# 04_-_RGB_LED_MATRIX.net
KiCad netlist of a schematic drawn in Altium Designer
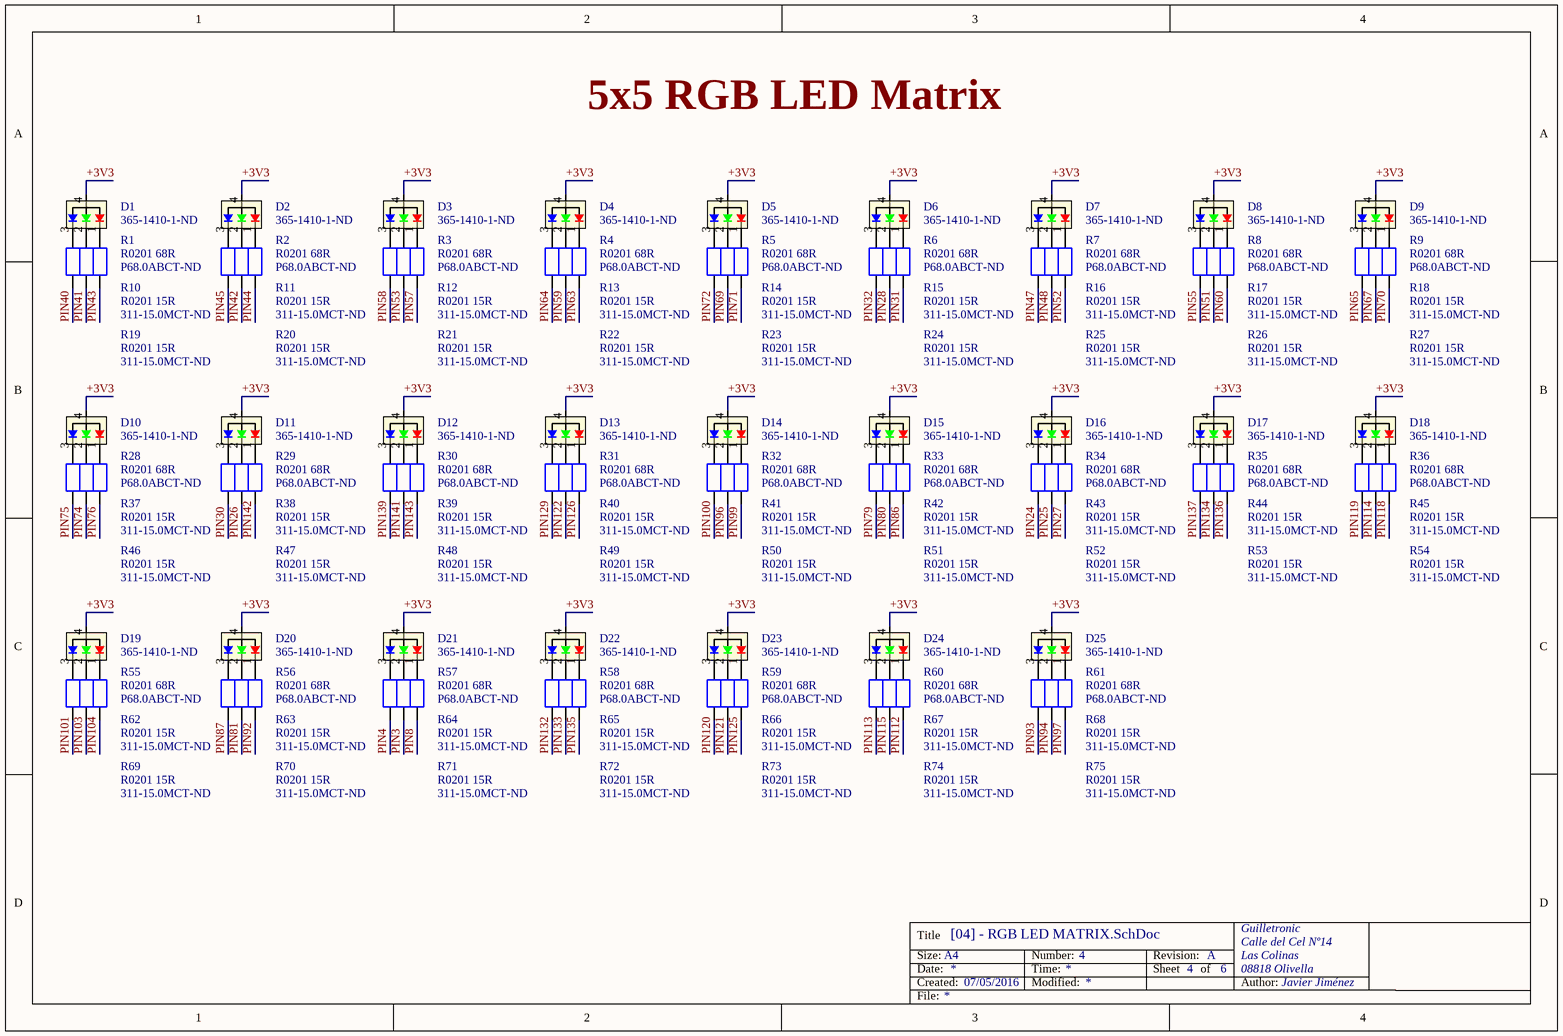
[diagram p0: [04] - RGB LED MATRIX.SchDoc]

(export (version "E")
  (design (tool "Eeschema 10.0.6"))
  (components
    (comp (ref "D1")
      (value "LED RGB")
      (footprint "LED RGB")
      (description "LED RGB DIFFUSED 4SMD R/A")
      (fields (field (name "SUPPLIER PART NUMBER 1") "365-1410-1-ND"))
      (libsource (lib "GUILLETRONIC") (part "LED RGB"))
    )
    (comp (ref "D2")
      (value "LED RGB")
      (footprint "LED RGB")
      (description "LED RGB DIFFUSED 4SMD R/A")
      (fields (field (name "SUPPLIER PART NUMBER 1") "365-1410-1-ND"))
      (libsource (lib "GUILLETRONIC") (part "LED RGB"))
    )
    (comp (ref "D3")
      (value "LED RGB")
      (footprint "LED RGB")
      (description "LED RGB DIFFUSED 4SMD R/A")
      (fields (field (name "SUPPLIER PART NUMBER 1") "365-1410-1-ND"))
      (libsource (lib "GUILLETRONIC") (part "LED RGB"))
    )
    (comp (ref "D4")
      (value "LED RGB")
      (footprint "LED RGB")
      (description "LED RGB DIFFUSED 4SMD R/A")
      (fields (field (name "SUPPLIER PART NUMBER 1") "365-1410-1-ND"))
      (libsource (lib "GUILLETRONIC") (part "LED RGB"))
    )
    (comp (ref "D5")
      (value "LED RGB")
      (footprint "LED RGB")
      (description "LED RGB DIFFUSED 4SMD R/A")
      (fields (field (name "SUPPLIER PART NUMBER 1") "365-1410-1-ND"))
      (libsource (lib "GUILLETRONIC") (part "LED RGB"))
    )
    (comp (ref "D6")
      (value "LED RGB")
      (footprint "LED RGB")
      (description "LED RGB DIFFUSED 4SMD R/A")
      (fields (field (name "SUPPLIER PART NUMBER 1") "365-1410-1-ND"))
      (libsource (lib "GUILLETRONIC") (part "LED RGB"))
    )
    (comp (ref "D7")
      (value "LED RGB")
      (footprint "LED RGB")
      (description "LED RGB DIFFUSED 4SMD R/A")
      (fields (field (name "SUPPLIER PART NUMBER 1") "365-1410-1-ND"))
      (libsource (lib "GUILLETRONIC") (part "LED RGB"))
    )
    (comp (ref "D8")
      (value "LED RGB")
      (footprint "LED RGB")
      (description "LED RGB DIFFUSED 4SMD R/A")
      (fields (field (name "SUPPLIER PART NUMBER 1") "365-1410-1-ND"))
      (libsource (lib "GUILLETRONIC") (part "LED RGB"))
    )
    (comp (ref "D9")
      (value "LED RGB")
      (footprint "LED RGB")
      (description "LED RGB DIFFUSED 4SMD R/A")
      (fields (field (name "SUPPLIER PART NUMBER 1") "365-1410-1-ND"))
      (libsource (lib "GUILLETRONIC") (part "LED RGB"))
    )
    (comp (ref "D10")
      (value "LED RGB")
      (footprint "LED RGB")
      (description "LED RGB DIFFUSED 4SMD R/A")
      (fields (field (name "SUPPLIER PART NUMBER 1") "365-1410-1-ND"))
      (libsource (lib "GUILLETRONIC") (part "LED RGB"))
    )
    (comp (ref "D11")
      (value "LED RGB")
      (footprint "LED RGB")
      (description "LED RGB DIFFUSED 4SMD R/A")
      (fields (field (name "SUPPLIER PART NUMBER 1") "365-1410-1-ND"))
      (libsource (lib "GUILLETRONIC") (part "LED RGB"))
    )
    (comp (ref "D12")
      (value "LED RGB")
      (footprint "LED RGB")
      (description "LED RGB DIFFUSED 4SMD R/A")
      (fields (field (name "SUPPLIER PART NUMBER 1") "365-1410-1-ND"))
      (libsource (lib "GUILLETRONIC") (part "LED RGB"))
    )
    (comp (ref "D13")
      (value "LED RGB")
      (footprint "LED RGB")
      (description "LED RGB DIFFUSED 4SMD R/A")
      (fields (field (name "SUPPLIER PART NUMBER 1") "365-1410-1-ND"))
      (libsource (lib "GUILLETRONIC") (part "LED RGB"))
    )
    (comp (ref "D14")
      (value "LED RGB")
      (footprint "LED RGB")
      (description "LED RGB DIFFUSED 4SMD R/A")
      (fields (field (name "SUPPLIER PART NUMBER 1") "365-1410-1-ND"))
      (libsource (lib "GUILLETRONIC") (part "LED RGB"))
    )
    (comp (ref "D15")
      (value "LED RGB")
      (footprint "LED RGB")
      (description "LED RGB DIFFUSED 4SMD R/A")
      (fields (field (name "SUPPLIER PART NUMBER 1") "365-1410-1-ND"))
      (libsource (lib "GUILLETRONIC") (part "LED RGB"))
    )
    (comp (ref "D16")
      (value "LED RGB")
      (footprint "LED RGB")
      (description "LED RGB DIFFUSED 4SMD R/A")
      (fields (field (name "SUPPLIER PART NUMBER 1") "365-1410-1-ND"))
      (libsource (lib "GUILLETRONIC") (part "LED RGB"))
    )
    (comp (ref "D17")
      (value "LED RGB")
      (footprint "LED RGB")
      (description "LED RGB DIFFUSED 4SMD R/A")
      (fields (field (name "SUPPLIER PART NUMBER 1") "365-1410-1-ND"))
      (libsource (lib "GUILLETRONIC") (part "LED RGB"))
    )
    (comp (ref "D18")
      (value "LED RGB")
      (footprint "LED RGB")
      (description "LED RGB DIFFUSED 4SMD R/A")
      (fields (field (name "SUPPLIER PART NUMBER 1") "365-1410-1-ND"))
      (libsource (lib "GUILLETRONIC") (part "LED RGB"))
    )
    (comp (ref "D19")
      (value "LED RGB")
      (footprint "LED RGB")
      (description "LED RGB DIFFUSED 4SMD R/A")
      (fields (field (name "SUPPLIER PART NUMBER 1") "365-1410-1-ND"))
      (libsource (lib "GUILLETRONIC") (part "LED RGB"))
    )
    (comp (ref "D20")
      (value "LED RGB")
      (footprint "LED RGB")
      (description "LED RGB DIFFUSED 4SMD R/A")
      (fields (field (name "SUPPLIER PART NUMBER 1") "365-1410-1-ND"))
      (libsource (lib "GUILLETRONIC") (part "LED RGB"))
    )
    (comp (ref "D21")
      (value "LED RGB")
      (footprint "LED RGB")
      (description "LED RGB DIFFUSED 4SMD R/A")
      (fields (field (name "SUPPLIER PART NUMBER 1") "365-1410-1-ND"))
      (libsource (lib "GUILLETRONIC") (part "LED RGB"))
    )
    (comp (ref "D22")
      (value "LED RGB")
      (footprint "LED RGB")
      (description "LED RGB DIFFUSED 4SMD R/A")
      (fields (field (name "SUPPLIER PART NUMBER 1") "365-1410-1-ND"))
      (libsource (lib "GUILLETRONIC") (part "LED RGB"))
    )
    (comp (ref "D23")
      (value "LED RGB")
      (footprint "LED RGB")
      (description "LED RGB DIFFUSED 4SMD R/A")
      (fields (field (name "SUPPLIER PART NUMBER 1") "365-1410-1-ND"))
      (libsource (lib "GUILLETRONIC") (part "LED RGB"))
    )
    (comp (ref "D24")
      (value "LED RGB")
      (footprint "LED RGB")
      (description "LED RGB DIFFUSED 4SMD R/A")
      (fields (field (name "SUPPLIER PART NUMBER 1") "365-1410-1-ND"))
      (libsource (lib "GUILLETRONIC") (part "LED RGB"))
    )
    (comp (ref "D25")
      (value "LED RGB")
      (footprint "LED RGB")
      (description "LED RGB DIFFUSED 4SMD R/A")
      (fields (field (name "SUPPLIER PART NUMBER 1") "365-1410-1-ND"))
      (libsource (lib "GUILLETRONIC") (part "LED RGB"))
    )
    (comp (ref "R1")
      (value "R0201 68R")
      (footprint "R0201")
      (fields (field (name "TOLERANCE") "±1%") (field (name "SUPPLIER PART NUMBER 1") "P68.0ABCT-ND"))
      (libsource (lib "GUILLETRONIC") (part "R0201 68R"))
    )
    (comp (ref "R2")
      (value "R0201 68R")
      (footprint "R0201")
      (fields (field (name "TOLERANCE") "±1%") (field (name "SUPPLIER PART NUMBER 1") "P68.0ABCT-ND"))
      (libsource (lib "GUILLETRONIC") (part "R0201 68R"))
    )
    (comp (ref "R3")
      (value "R0201 68R")
      (footprint "R0201")
      (fields (field (name "TOLERANCE") "±1%") (field (name "SUPPLIER PART NUMBER 1") "P68.0ABCT-ND"))
      (libsource (lib "GUILLETRONIC") (part "R0201 68R"))
    )
    (comp (ref "R4")
      (value "R0201 68R")
      (footprint "R0201")
      (fields (field (name "TOLERANCE") "±1%") (field (name "SUPPLIER PART NUMBER 1") "P68.0ABCT-ND"))
      (libsource (lib "GUILLETRONIC") (part "R0201 68R"))
    )
    (comp (ref "R5")
      (value "R0201 68R")
      (footprint "R0201")
      (fields (field (name "TOLERANCE") "±1%") (field (name "SUPPLIER PART NUMBER 1") "P68.0ABCT-ND"))
      (libsource (lib "GUILLETRONIC") (part "R0201 68R"))
    )
    (comp (ref "R6")
      (value "R0201 68R")
      (footprint "R0201")
      (fields (field (name "TOLERANCE") "±1%") (field (name "SUPPLIER PART NUMBER 1") "P68.0ABCT-ND"))
      (libsource (lib "GUILLETRONIC") (part "R0201 68R"))
    )
    (comp (ref "R7")
      (value "R0201 68R")
      (footprint "R0201")
      (fields (field (name "TOLERANCE") "±1%") (field (name "SUPPLIER PART NUMBER 1") "P68.0ABCT-ND"))
      (libsource (lib "GUILLETRONIC") (part "R0201 68R"))
    )
    (comp (ref "R8")
      (value "R0201 68R")
      (footprint "R0201")
      (fields (field (name "TOLERANCE") "±1%") (field (name "SUPPLIER PART NUMBER 1") "P68.0ABCT-ND"))
      (libsource (lib "GUILLETRONIC") (part "R0201 68R"))
    )
    (comp (ref "R9")
      (value "R0201 68R")
      (footprint "R0201")
      (fields (field (name "TOLERANCE") "±1%") (field (name "SUPPLIER PART NUMBER 1") "P68.0ABCT-ND"))
      (libsource (lib "GUILLETRONIC") (part "R0201 68R"))
    )
    (comp (ref "R10")
      (value "R0201 15R")
      (footprint "R0201")
      (fields (field (name "TOLERANCE") "±1%") (field (name "SUPPLIER PART NUMBER 1") "311-15.0MCT-ND"))
      (libsource (lib "GUILLETRONIC") (part "R0201 15R"))
    )
    (comp (ref "R11")
      (value "R0201 15R")
      (footprint "R0201")
      (fields (field (name "TOLERANCE") "±1%") (field (name "SUPPLIER PART NUMBER 1") "311-15.0MCT-ND"))
      (libsource (lib "GUILLETRONIC") (part "R0201 15R"))
    )
    (comp (ref "R12")
      (value "R0201 15R")
      (footprint "R0201")
      (fields (field (name "TOLERANCE") "±1%") (field (name "SUPPLIER PART NUMBER 1") "311-15.0MCT-ND"))
      (libsource (lib "GUILLETRONIC") (part "R0201 15R"))
    )
    (comp (ref "R13")
      (value "R0201 15R")
      (footprint "R0201")
      (fields (field (name "TOLERANCE") "±1%") (field (name "SUPPLIER PART NUMBER 1") "311-15.0MCT-ND"))
      (libsource (lib "GUILLETRONIC") (part "R0201 15R"))
    )
    (comp (ref "R14")
      (value "R0201 15R")
      (footprint "R0201")
      (fields (field (name "TOLERANCE") "±1%") (field (name "SUPPLIER PART NUMBER 1") "311-15.0MCT-ND"))
      (libsource (lib "GUILLETRONIC") (part "R0201 15R"))
    )
    (comp (ref "R15")
      (value "R0201 15R")
      (footprint "R0201")
      (fields (field (name "TOLERANCE") "±1%") (field (name "SUPPLIER PART NUMBER 1") "311-15.0MCT-ND"))
      (libsource (lib "GUILLETRONIC") (part "R0201 15R"))
    )
    (comp (ref "R16")
      (value "R0201 15R")
      (footprint "R0201")
      (fields (field (name "TOLERANCE") "±1%") (field (name "SUPPLIER PART NUMBER 1") "311-15.0MCT-ND"))
      (libsource (lib "GUILLETRONIC") (part "R0201 15R"))
    )
    (comp (ref "R17")
      (value "R0201 15R")
      (footprint "R0201")
      (fields (field (name "TOLERANCE") "±1%") (field (name "SUPPLIER PART NUMBER 1") "311-15.0MCT-ND"))
      (libsource (lib "GUILLETRONIC") (part "R0201 15R"))
    )
    (comp (ref "R18")
      (value "R0201 15R")
      (footprint "R0201")
      (fields (field (name "TOLERANCE") "±1%") (field (name "SUPPLIER PART NUMBER 1") "311-15.0MCT-ND"))
      (libsource (lib "GUILLETRONIC") (part "R0201 15R"))
    )
    (comp (ref "R19")
      (value "R0201 15R")
      (footprint "R0201")
      (fields (field (name "TOLERANCE") "±1%") (field (name "SUPPLIER PART NUMBER 1") "311-15.0MCT-ND"))
      (libsource (lib "GUILLETRONIC") (part "R0201 15R"))
    )
    (comp (ref "R20")
      (value "R0201 15R")
      (footprint "R0201")
      (fields (field (name "TOLERANCE") "±1%") (field (name "SUPPLIER PART NUMBER 1") "311-15.0MCT-ND"))
      (libsource (lib "GUILLETRONIC") (part "R0201 15R"))
    )
    (comp (ref "R21")
      (value "R0201 15R")
      (footprint "R0201")
      (fields (field (name "TOLERANCE") "±1%") (field (name "SUPPLIER PART NUMBER 1") "311-15.0MCT-ND"))
      (libsource (lib "GUILLETRONIC") (part "R0201 15R"))
    )
    (comp (ref "R22")
      (value "R0201 15R")
      (footprint "R0201")
      (fields (field (name "TOLERANCE") "±1%") (field (name "SUPPLIER PART NUMBER 1") "311-15.0MCT-ND"))
      (libsource (lib "GUILLETRONIC") (part "R0201 15R"))
    )
    (comp (ref "R23")
      (value "R0201 15R")
      (footprint "R0201")
      (fields (field (name "TOLERANCE") "±1%") (field (name "SUPPLIER PART NUMBER 1") "311-15.0MCT-ND"))
      (libsource (lib "GUILLETRONIC") (part "R0201 15R"))
    )
    (comp (ref "R24")
      (value "R0201 15R")
      (footprint "R0201")
      (fields (field (name "TOLERANCE") "±1%") (field (name "SUPPLIER PART NUMBER 1") "311-15.0MCT-ND"))
      (libsource (lib "GUILLETRONIC") (part "R0201 15R"))
    )
    (comp (ref "R25")
      (value "R0201 15R")
      (footprint "R0201")
      (fields (field (name "TOLERANCE") "±1%") (field (name "SUPPLIER PART NUMBER 1") "311-15.0MCT-ND"))
      (libsource (lib "GUILLETRONIC") (part "R0201 15R"))
    )
    (comp (ref "R26")
      (value "R0201 15R")
      (footprint "R0201")
      (fields (field (name "TOLERANCE") "±1%") (field (name "SUPPLIER PART NUMBER 1") "311-15.0MCT-ND"))
      (libsource (lib "GUILLETRONIC") (part "R0201 15R"))
    )
    (comp (ref "R27")
      (value "R0201 15R")
      (footprint "R0201")
      (fields (field (name "TOLERANCE") "±1%") (field (name "SUPPLIER PART NUMBER 1") "311-15.0MCT-ND"))
      (libsource (lib "GUILLETRONIC") (part "R0201 15R"))
    )
    (comp (ref "R28")
      (value "R0201 68R")
      (footprint "R0201")
      (fields (field (name "TOLERANCE") "±1%") (field (name "SUPPLIER PART NUMBER 1") "P68.0ABCT-ND"))
      (libsource (lib "GUILLETRONIC") (part "R0201 68R"))
    )
    (comp (ref "R29")
      (value "R0201 68R")
      (footprint "R0201")
      (fields (field (name "TOLERANCE") "±1%") (field (name "SUPPLIER PART NUMBER 1") "P68.0ABCT-ND"))
      (libsource (lib "GUILLETRONIC") (part "R0201 68R"))
    )
    (comp (ref "R30")
      (value "R0201 68R")
      (footprint "R0201")
      (fields (field (name "TOLERANCE") "±1%") (field (name "SUPPLIER PART NUMBER 1") "P68.0ABCT-ND"))
      (libsource (lib "GUILLETRONIC") (part "R0201 68R"))
    )
    (comp (ref "R31")
      (value "R0201 68R")
      (footprint "R0201")
      (fields (field (name "TOLERANCE") "±1%") (field (name "SUPPLIER PART NUMBER 1") "P68.0ABCT-ND"))
      (libsource (lib "GUILLETRONIC") (part "R0201 68R"))
    )
    (comp (ref "R32")
      (value "R0201 68R")
      (footprint "R0201")
      (fields (field (name "TOLERANCE") "±1%") (field (name "SUPPLIER PART NUMBER 1") "P68.0ABCT-ND"))
      (libsource (lib "GUILLETRONIC") (part "R0201 68R"))
    )
    (comp (ref "R33")
      (value "R0201 68R")
      (footprint "R0201")
      (fields (field (name "TOLERANCE") "±1%") (field (name "SUPPLIER PART NUMBER 1") "P68.0ABCT-ND"))
      (libsource (lib "GUILLETRONIC") (part "R0201 68R"))
    )
    (comp (ref "R34")
      (value "R0201 68R")
      (footprint "R0201")
      (fields (field (name "TOLERANCE") "±1%") (field (name "SUPPLIER PART NUMBER 1") "P68.0ABCT-ND"))
      (libsource (lib "GUILLETRONIC") (part "R0201 68R"))
    )
    (comp (ref "R35")
      (value "R0201 68R")
      (footprint "R0201")
      (fields (field (name "TOLERANCE") "±1%") (field (name "SUPPLIER PART NUMBER 1") "P68.0ABCT-ND"))
      (libsource (lib "GUILLETRONIC") (part "R0201 68R"))
    )
    (comp (ref "R36")
      (value "R0201 68R")
      (footprint "R0201")
      (fields (field (name "TOLERANCE") "±1%") (field (name "SUPPLIER PART NUMBER 1") "P68.0ABCT-ND"))
      (libsource (lib "GUILLETRONIC") (part "R0201 68R"))
    )
    (comp (ref "R37")
      (value "R0201 15R")
      (footprint "R0201")
      (fields (field (name "TOLERANCE") "±1%") (field (name "SUPPLIER PART NUMBER 1") "311-15.0MCT-ND"))
      (libsource (lib "GUILLETRONIC") (part "R0201 15R"))
    )
    (comp (ref "R38")
      (value "R0201 15R")
      (footprint "R0201")
      (fields (field (name "TOLERANCE") "±1%") (field (name "SUPPLIER PART NUMBER 1") "311-15.0MCT-ND"))
      (libsource (lib "GUILLETRONIC") (part "R0201 15R"))
    )
    (comp (ref "R39")
      (value "R0201 15R")
      (footprint "R0201")
      (fields (field (name "TOLERANCE") "±1%") (field (name "SUPPLIER PART NUMBER 1") "311-15.0MCT-ND"))
      (libsource (lib "GUILLETRONIC") (part "R0201 15R"))
    )
    (comp (ref "R40")
      (value "R0201 15R")
      (footprint "R0201")
      (fields (field (name "TOLERANCE") "±1%") (field (name "SUPPLIER PART NUMBER 1") "311-15.0MCT-ND"))
      (libsource (lib "GUILLETRONIC") (part "R0201 15R"))
    )
    (comp (ref "R41")
      (value "R0201 15R")
      (footprint "R0201")
      (fields (field (name "TOLERANCE") "±1%") (field (name "SUPPLIER PART NUMBER 1") "311-15.0MCT-ND"))
      (libsource (lib "GUILLETRONIC") (part "R0201 15R"))
    )
    (comp (ref "R42")
      (value "R0201 15R")
      (footprint "R0201")
      (fields (field (name "TOLERANCE") "±1%") (field (name "SUPPLIER PART NUMBER 1") "311-15.0MCT-ND"))
      (libsource (lib "GUILLETRONIC") (part "R0201 15R"))
    )
    (comp (ref "R43")
      (value "R0201 15R")
      (footprint "R0201")
      (fields (field (name "TOLERANCE") "±1%") (field (name "SUPPLIER PART NUMBER 1") "311-15.0MCT-ND"))
      (libsource (lib "GUILLETRONIC") (part "R0201 15R"))
    )
    (comp (ref "R44")
      (value "R0201 15R")
      (footprint "R0201")
      (fields (field (name "TOLERANCE") "±1%") (field (name "SUPPLIER PART NUMBER 1") "311-15.0MCT-ND"))
      (libsource (lib "GUILLETRONIC") (part "R0201 15R"))
    )
    (comp (ref "R45")
      (value "R0201 15R")
      (footprint "R0201")
      (fields (field (name "TOLERANCE") "±1%") (field (name "SUPPLIER PART NUMBER 1") "311-15.0MCT-ND"))
      (libsource (lib "GUILLETRONIC") (part "R0201 15R"))
    )
    (comp (ref "R46")
      (value "R0201 15R")
      (footprint "R0201")
      (fields (field (name "TOLERANCE") "±1%") (field (name "SUPPLIER PART NUMBER 1") "311-15.0MCT-ND"))
      (libsource (lib "GUILLETRONIC") (part "R0201 15R"))
    )
    (comp (ref "R47")
      (value "R0201 15R")
      (footprint "R0201")
      (fields (field (name "TOLERANCE") "±1%") (field (name "SUPPLIER PART NUMBER 1") "311-15.0MCT-ND"))
      (libsource (lib "GUILLETRONIC") (part "R0201 15R"))
    )
    (comp (ref "R48")
      (value "R0201 15R")
      (footprint "R0201")
      (fields (field (name "TOLERANCE") "±1%") (field (name "SUPPLIER PART NUMBER 1") "311-15.0MCT-ND"))
      (libsource (lib "GUILLETRONIC") (part "R0201 15R"))
    )
    (comp (ref "R49")
      (value "R0201 15R")
      (footprint "R0201")
      (fields (field (name "TOLERANCE") "±1%") (field (name "SUPPLIER PART NUMBER 1") "311-15.0MCT-ND"))
      (libsource (lib "GUILLETRONIC") (part "R0201 15R"))
    )
    (comp (ref "R50")
      (value "R0201 15R")
      (footprint "R0201")
      (fields (field (name "TOLERANCE") "±1%") (field (name "SUPPLIER PART NUMBER 1") "311-15.0MCT-ND"))
      (libsource (lib "GUILLETRONIC") (part "R0201 15R"))
    )
    (comp (ref "R51")
      (value "R0201 15R")
      (footprint "R0201")
      (fields (field (name "TOLERANCE") "±1%") (field (name "SUPPLIER PART NUMBER 1") "311-15.0MCT-ND"))
      (libsource (lib "GUILLETRONIC") (part "R0201 15R"))
    )
    (comp (ref "R52")
      (value "R0201 15R")
      (footprint "R0201")
      (fields (field (name "TOLERANCE") "±1%") (field (name "SUPPLIER PART NUMBER 1") "311-15.0MCT-ND"))
      (libsource (lib "GUILLETRONIC") (part "R0201 15R"))
    )
    (comp (ref "R53")
      (value "R0201 15R")
      (footprint "R0201")
      (fields (field (name "TOLERANCE") "±1%") (field (name "SUPPLIER PART NUMBER 1") "311-15.0MCT-ND"))
      (libsource (lib "GUILLETRONIC") (part "R0201 15R"))
    )
    (comp (ref "R54")
      (value "R0201 15R")
      (footprint "R0201")
      (fields (field (name "TOLERANCE") "±1%") (field (name "SUPPLIER PART NUMBER 1") "311-15.0MCT-ND"))
      (libsource (lib "GUILLETRONIC") (part "R0201 15R"))
    )
    (comp (ref "R55")
      (value "R0201 68R")
      (footprint "R0201")
      (fields (field (name "TOLERANCE") "±1%") (field (name "SUPPLIER PART NUMBER 1") "P68.0ABCT-ND"))
      (libsource (lib "GUILLETRONIC") (part "R0201 68R"))
    )
    (comp (ref "R56")
      (value "R0201 68R")
      (footprint "R0201")
      (fields (field (name "TOLERANCE") "±1%") (field (name "SUPPLIER PART NUMBER 1") "P68.0ABCT-ND"))
      (libsource (lib "GUILLETRONIC") (part "R0201 68R"))
    )
    (comp (ref "R57")
      (value "R0201 68R")
      (footprint "R0201")
      (fields (field (name "TOLERANCE") "±1%") (field (name "SUPPLIER PART NUMBER 1") "P68.0ABCT-ND"))
      (libsource (lib "GUILLETRONIC") (part "R0201 68R"))
    )
    (comp (ref "R58")
      (value "R0201 68R")
      (footprint "R0201")
      (fields (field (name "TOLERANCE") "±1%") (field (name "SUPPLIER PART NUMBER 1") "P68.0ABCT-ND"))
      (libsource (lib "GUILLETRONIC") (part "R0201 68R"))
    )
    (comp (ref "R59")
      (value "R0201 68R")
      (footprint "R0201")
      (fields (field (name "TOLERANCE") "±1%") (field (name "SUPPLIER PART NUMBER 1") "P68.0ABCT-ND"))
      (libsource (lib "GUILLETRONIC") (part "R0201 68R"))
    )
    (comp (ref "R60")
      (value "R0201 68R")
      (footprint "R0201")
      (fields (field (name "TOLERANCE") "±1%") (field (name "SUPPLIER PART NUMBER 1") "P68.0ABCT-ND"))
      (libsource (lib "GUILLETRONIC") (part "R0201 68R"))
    )
    (comp (ref "R61")
      (value "R0201 68R")
      (footprint "R0201")
      (fields (field (name "TOLERANCE") "±1%") (field (name "SUPPLIER PART NUMBER 1") "P68.0ABCT-ND"))
      (libsource (lib "GUILLETRONIC") (part "R0201 68R"))
    )
    (comp (ref "R62")
      (value "R0201 15R")
      (footprint "R0201")
      (fields (field (name "TOLERANCE") "±1%") (field (name "SUPPLIER PART NUMBER 1") "311-15.0MCT-ND"))
      (libsource (lib "GUILLETRONIC") (part "R0201 15R"))
    )
    (comp (ref "R63")
      (value "R0201 15R")
      (footprint "R0201")
      (fields (field (name "TOLERANCE") "±1%") (field (name "SUPPLIER PART NUMBER 1") "311-15.0MCT-ND"))
      (libsource (lib "GUILLETRONIC") (part "R0201 15R"))
    )
    (comp (ref "R64")
      (value "R0201 15R")
      (footprint "R0201")
      (fields (field (name "TOLERANCE") "±1%") (field (name "SUPPLIER PART NUMBER 1") "311-15.0MCT-ND"))
      (libsource (lib "GUILLETRONIC") (part "R0201 15R"))
    )
    (comp (ref "R65")
      (value "R0201 15R")
      (footprint "R0201")
      (fields (field (name "TOLERANCE") "±1%") (field (name "SUPPLIER PART NUMBER 1") "311-15.0MCT-ND"))
      (libsource (lib "GUILLETRONIC") (part "R0201 15R"))
    )
    (comp (ref "R66")
      (value "R0201 15R")
      (footprint "R0201")
      (fields (field (name "TOLERANCE") "±1%") (field (name "SUPPLIER PART NUMBER 1") "311-15.0MCT-ND"))
      (libsource (lib "GUILLETRONIC") (part "R0201 15R"))
    )
    (comp (ref "R67")
      (value "R0201 15R")
      (footprint "R0201")
      (fields (field (name "TOLERANCE") "±1%") (field (name "SUPPLIER PART NUMBER 1") "311-15.0MCT-ND"))
      (libsource (lib "GUILLETRONIC") (part "R0201 15R"))
    )
    (comp (ref "R68")
      (value "R0201 15R")
      (footprint "R0201")
      (fields (field (name "TOLERANCE") "±1%") (field (name "SUPPLIER PART NUMBER 1") "311-15.0MCT-ND"))
      (libsource (lib "GUILLETRONIC") (part "R0201 15R"))
    )
    (comp (ref "R69")
      (value "R0201 15R")
      (footprint "R0201")
      (fields (field (name "TOLERANCE") "±1%") (field (name "SUPPLIER PART NUMBER 1") "311-15.0MCT-ND"))
      (libsource (lib "GUILLETRONIC") (part "R0201 15R"))
    )
    (comp (ref "R70")
      (value "R0201 15R")
      (footprint "R0201")
      (fields (field (name "TOLERANCE") "±1%") (field (name "SUPPLIER PART NUMBER 1") "311-15.0MCT-ND"))
      (libsource (lib "GUILLETRONIC") (part "R0201 15R"))
    )
    (comp (ref "R71")
      (value "R0201 15R")
      (footprint "R0201")
      (fields (field (name "TOLERANCE") "±1%") (field (name "SUPPLIER PART NUMBER 1") "311-15.0MCT-ND"))
      (libsource (lib "GUILLETRONIC") (part "R0201 15R"))
    )
    (comp (ref "R72")
      (value "R0201 15R")
      (footprint "R0201")
      (fields (field (name "TOLERANCE") "±1%") (field (name "SUPPLIER PART NUMBER 1") "311-15.0MCT-ND"))
      (libsource (lib "GUILLETRONIC") (part "R0201 15R"))
    )
    (comp (ref "R73")
      (value "R0201 15R")
      (footprint "R0201")
      (fields (field (name "TOLERANCE") "±1%") (field (name "SUPPLIER PART NUMBER 1") "311-15.0MCT-ND"))
      (libsource (lib "GUILLETRONIC") (part "R0201 15R"))
    )
    (comp (ref "R74")
      (value "R0201 15R")
      (footprint "R0201")
      (fields (field (name "TOLERANCE") "±1%") (field (name "SUPPLIER PART NUMBER 1") "311-15.0MCT-ND"))
      (libsource (lib "GUILLETRONIC") (part "R0201 15R"))
    )
    (comp (ref "R75")
      (value "R0201 15R")
      (footprint "R0201")
      (fields (field (name "TOLERANCE") "±1%") (field (name "SUPPLIER PART NUMBER 1") "311-15.0MCT-ND"))
      (libsource (lib "GUILLETRONIC") (part "R0201 15R"))
    )
  )
  (nets
    (net (code "1") (name "/+3V3") (class "Default")
      (node (ref "D1") (pin "4") (pinfunction "ANODE_4") (pintype "passive"))
      (node (ref "D10") (pin "4") (pinfunction "ANODE_4") (pintype "passive"))
      (node (ref "D11") (pin "4") (pinfunction "ANODE_4") (pintype "passive"))
      (node (ref "D12") (pin "4") (pinfunction "ANODE_4") (pintype "passive"))
      (node (ref "D13") (pin "4") (pinfunction "ANODE_4") (pintype "passive"))
      (node (ref "D14") (pin "4") (pinfunction "ANODE_4") (pintype "passive"))
      (node (ref "D15") (pin "4") (pinfunction "ANODE_4") (pintype "passive"))
      (node (ref "D16") (pin "4") (pinfunction "ANODE_4") (pintype "passive"))
      (node (ref "D17") (pin "4") (pinfunction "ANODE_4") (pintype "passive"))
      (node (ref "D18") (pin "4") (pinfunction "ANODE_4") (pintype "passive"))
      (node (ref "D19") (pin "4") (pinfunction "ANODE_4") (pintype "passive"))
      (node (ref "D2") (pin "4") (pinfunction "ANODE_4") (pintype "passive"))
      (node (ref "D20") (pin "4") (pinfunction "ANODE_4") (pintype "passive"))
      (node (ref "D21") (pin "4") (pinfunction "ANODE_4") (pintype "passive"))
      (node (ref "D22") (pin "4") (pinfunction "ANODE_4") (pintype "passive"))
      (node (ref "D23") (pin "4") (pinfunction "ANODE_4") (pintype "passive"))
      (node (ref "D24") (pin "4") (pinfunction "ANODE_4") (pintype "passive"))
      (node (ref "D25") (pin "4") (pinfunction "ANODE_4") (pintype "passive"))
      (node (ref "D3") (pin "4") (pinfunction "ANODE_4") (pintype "passive"))
      (node (ref "D4") (pin "4") (pinfunction "ANODE_4") (pintype "passive"))
      (node (ref "D5") (pin "4") (pinfunction "ANODE_4") (pintype "passive"))
      (node (ref "D6") (pin "4") (pinfunction "ANODE_4") (pintype "passive"))
      (node (ref "D7") (pin "4") (pinfunction "ANODE_4") (pintype "passive"))
      (node (ref "D8") (pin "4") (pinfunction "ANODE_4") (pintype "passive"))
      (node (ref "D9") (pin "4") (pinfunction "ANODE_4") (pintype "passive"))
    )
    (net (code "2") (name "/PIN3") (class "Default")
      (node (ref "R64") (pin "2") (pinfunction "2_2") (pintype "passive"))
    )
    (net (code "3") (name "/PIN4") (class "Default")
      (node (ref "R71") (pin "2") (pinfunction "2_2") (pintype "passive"))
    )
    (net (code "4") (name "/PIN8") (class "Default")
      (node (ref "R57") (pin "2") (pinfunction "2_2") (pintype "passive"))
    )
    (net (code "5") (name "/PIN24") (class "Default")
      (node (ref "R52") (pin "2") (pinfunction "2_2") (pintype "passive"))
    )
    (net (code "6") (name "/PIN25") (class "Default")
      (node (ref "R43") (pin "2") (pinfunction "2_2") (pintype "passive"))
    )
    (net (code "7") (name "/PIN26") (class "Default")
      (node (ref "R38") (pin "2") (pinfunction "2_2") (pintype "passive"))
    )
    (net (code "8") (name "/PIN27") (class "Default")
      (node (ref "R34") (pin "2") (pinfunction "2_2") (pintype "passive"))
    )
    (net (code "9") (name "/PIN28") (class "Default")
      (node (ref "R15") (pin "2") (pinfunction "2_2") (pintype "passive"))
    )
    (net (code "10") (name "/PIN30") (class "Default")
      (node (ref "R47") (pin "2") (pinfunction "2_2") (pintype "passive"))
    )
    (net (code "11") (name "/PIN31") (class "Default")
      (node (ref "R6") (pin "2") (pinfunction "2_2") (pintype "passive"))
    )
    (net (code "12") (name "/PIN32") (class "Default")
      (node (ref "R24") (pin "2") (pinfunction "2_2") (pintype "passive"))
    )
    (net (code "13") (name "/PIN40") (class "Default")
      (node (ref "R19") (pin "2") (pinfunction "2_2") (pintype "passive"))
    )
    (net (code "14") (name "/PIN41") (class "Default")
      (node (ref "R10") (pin "2") (pinfunction "2_2") (pintype "passive"))
    )
    (net (code "15") (name "/PIN42") (class "Default")
      (node (ref "R11") (pin "2") (pinfunction "2_2") (pintype "passive"))
    )
    (net (code "16") (name "/PIN43") (class "Default")
      (node (ref "R1") (pin "2") (pinfunction "2_2") (pintype "passive"))
    )
    (net (code "17") (name "/PIN44") (class "Default")
      (node (ref "R2") (pin "2") (pinfunction "2_2") (pintype "passive"))
    )
    (net (code "18") (name "/PIN45") (class "Default")
      (node (ref "R20") (pin "2") (pinfunction "2_2") (pintype "passive"))
    )
    (net (code "19") (name "/PIN47") (class "Default")
      (node (ref "R25") (pin "2") (pinfunction "2_2") (pintype "passive"))
    )
    (net (code "20") (name "/PIN48") (class "Default")
      (node (ref "R16") (pin "2") (pinfunction "2_2") (pintype "passive"))
    )
    (net (code "21") (name "/PIN51") (class "Default")
      (node (ref "R17") (pin "2") (pinfunction "2_2") (pintype "passive"))
    )
    (net (code "22") (name "/PIN52") (class "Default")
      (node (ref "R7") (pin "2") (pinfunction "2_2") (pintype "passive"))
    )
    (net (code "23") (name "/PIN53") (class "Default")
      (node (ref "R12") (pin "2") (pinfunction "2_2") (pintype "passive"))
    )
    (net (code "24") (name "/PIN55") (class "Default")
      (node (ref "R26") (pin "2") (pinfunction "2_2") (pintype "passive"))
    )
    (net (code "25") (name "/PIN57") (class "Default")
      (node (ref "R3") (pin "2") (pinfunction "2_2") (pintype "passive"))
    )
    (net (code "26") (name "/PIN58") (class "Default")
      (node (ref "R21") (pin "2") (pinfunction "2_2") (pintype "passive"))
    )
    (net (code "27") (name "/PIN59") (class "Default")
      (node (ref "R13") (pin "2") (pinfunction "2_2") (pintype "passive"))
    )
    (net (code "28") (name "/PIN60") (class "Default")
      (node (ref "R8") (pin "2") (pinfunction "2_2") (pintype "passive"))
    )
    (net (code "29") (name "/PIN63") (class "Default")
      (node (ref "R4") (pin "2") (pinfunction "2_2") (pintype "passive"))
    )
    (net (code "30") (name "/PIN64") (class "Default")
      (node (ref "R22") (pin "2") (pinfunction "2_2") (pintype "passive"))
    )
    (net (code "31") (name "/PIN65") (class "Default")
      (node (ref "R27") (pin "2") (pinfunction "2_2") (pintype "passive"))
    )
    (net (code "32") (name "/PIN67") (class "Default")
      (node (ref "R18") (pin "2") (pinfunction "2_2") (pintype "passive"))
    )
    (net (code "33") (name "/PIN69") (class "Default")
      (node (ref "R14") (pin "2") (pinfunction "2_2") (pintype "passive"))
    )
    (net (code "34") (name "/PIN70") (class "Default")
      (node (ref "R9") (pin "2") (pinfunction "2_2") (pintype "passive"))
    )
    (net (code "35") (name "/PIN71") (class "Default")
      (node (ref "R5") (pin "2") (pinfunction "2_2") (pintype "passive"))
    )
    (net (code "36") (name "/PIN72") (class "Default")
      (node (ref "R23") (pin "2") (pinfunction "2_2") (pintype "passive"))
    )
    (net (code "37") (name "/PIN74") (class "Default")
      (node (ref "R37") (pin "2") (pinfunction "2_2") (pintype "passive"))
    )
    (net (code "38") (name "/PIN75") (class "Default")
      (node (ref "R46") (pin "2") (pinfunction "2_2") (pintype "passive"))
    )
    (net (code "39") (name "/PIN76") (class "Default")
      (node (ref "R28") (pin "2") (pinfunction "2_2") (pintype "passive"))
    )
    (net (code "40") (name "/PIN79") (class "Default")
      (node (ref "R51") (pin "2") (pinfunction "2_2") (pintype "passive"))
    )
    (net (code "41") (name "/PIN80") (class "Default")
      (node (ref "R42") (pin "2") (pinfunction "2_2") (pintype "passive"))
    )
    (net (code "42") (name "/PIN81") (class "Default")
      (node (ref "R63") (pin "2") (pinfunction "2_2") (pintype "passive"))
    )
    (net (code "43") (name "/PIN86") (class "Default")
      (node (ref "R33") (pin "2") (pinfunction "2_2") (pintype "passive"))
    )
    (net (code "44") (name "/PIN87") (class "Default")
      (node (ref "R70") (pin "2") (pinfunction "2_2") (pintype "passive"))
    )
    (net (code "45") (name "/PIN92") (class "Default")
      (node (ref "R56") (pin "2") (pinfunction "2_2") (pintype "passive"))
    )
    (net (code "46") (name "/PIN93") (class "Default")
      (node (ref "R75") (pin "2") (pinfunction "2_2") (pintype "passive"))
    )
    (net (code "47") (name "/PIN94") (class "Default")
      (node (ref "R68") (pin "2") (pinfunction "2_2") (pintype "passive"))
    )
    (net (code "48") (name "/PIN96") (class "Default")
      (node (ref "R41") (pin "2") (pinfunction "2_2") (pintype "passive"))
    )
    (net (code "49") (name "/PIN97") (class "Default")
      (node (ref "R61") (pin "2") (pinfunction "2_2") (pintype "passive"))
    )
    (net (code "50") (name "/PIN99") (class "Default")
      (node (ref "R32") (pin "2") (pinfunction "2_2") (pintype "passive"))
    )
    (net (code "51") (name "/PIN100") (class "Default")
      (node (ref "R50") (pin "2") (pinfunction "2_2") (pintype "passive"))
    )
    (net (code "52") (name "/PIN101") (class "Default")
      (node (ref "R69") (pin "2") (pinfunction "2_2") (pintype "passive"))
    )
    (net (code "53") (name "/PIN103") (class "Default")
      (node (ref "R62") (pin "2") (pinfunction "2_2") (pintype "passive"))
    )
    (net (code "54") (name "/PIN104") (class "Default")
      (node (ref "R55") (pin "2") (pinfunction "2_2") (pintype "passive"))
    )
    (net (code "55") (name "/PIN112") (class "Default")
      (node (ref "R60") (pin "2") (pinfunction "2_2") (pintype "passive"))
    )
    (net (code "56") (name "/PIN113") (class "Default")
      (node (ref "R74") (pin "2") (pinfunction "2_2") (pintype "passive"))
    )
    (net (code "57") (name "/PIN114") (class "Default")
      (node (ref "R45") (pin "2") (pinfunction "2_2") (pintype "passive"))
    )
    (net (code "58") (name "/PIN115") (class "Default")
      (node (ref "R67") (pin "2") (pinfunction "2_2") (pintype "passive"))
    )
    (net (code "59") (name "/PIN118") (class "Default")
      (node (ref "R36") (pin "2") (pinfunction "2_2") (pintype "passive"))
    )
    (net (code "60") (name "/PIN119") (class "Default")
      (node (ref "R54") (pin "2") (pinfunction "2_2") (pintype "passive"))
    )
    (net (code "61") (name "/PIN120") (class "Default")
      (node (ref "R73") (pin "2") (pinfunction "2_2") (pintype "passive"))
    )
    (net (code "62") (name "/PIN121") (class "Default")
      (node (ref "R66") (pin "2") (pinfunction "2_2") (pintype "passive"))
    )
    (net (code "63") (name "/PIN122") (class "Default")
      (node (ref "R40") (pin "2") (pinfunction "2_2") (pintype "passive"))
    )
    (net (code "64") (name "/PIN125") (class "Default")
      (node (ref "R59") (pin "2") (pinfunction "2_2") (pintype "passive"))
    )
    (net (code "65") (name "/PIN126") (class "Default")
      (node (ref "R31") (pin "2") (pinfunction "2_2") (pintype "passive"))
    )
    (net (code "66") (name "/PIN129") (class "Default")
      (node (ref "R49") (pin "2") (pinfunction "2_2") (pintype "passive"))
    )
    (net (code "67") (name "/PIN132") (class "Default")
      (node (ref "R72") (pin "2") (pinfunction "2_2") (pintype "passive"))
    )
    (net (code "68") (name "/PIN133") (class "Default")
      (node (ref "R65") (pin "2") (pinfunction "2_2") (pintype "passive"))
    )
    (net (code "69") (name "/PIN134") (class "Default")
      (node (ref "R44") (pin "2") (pinfunction "2_2") (pintype "passive"))
    )
    (net (code "70") (name "/PIN135") (class "Default")
      (node (ref "R58") (pin "2") (pinfunction "2_2") (pintype "passive"))
    )
    (net (code "71") (name "/PIN136") (class "Default")
      (node (ref "R35") (pin "2") (pinfunction "2_2") (pintype "passive"))
    )
    (net (code "72") (name "/PIN137") (class "Default")
      (node (ref "R53") (pin "2") (pinfunction "2_2") (pintype "passive"))
    )
    (net (code "73") (name "/PIN139") (class "Default")
      (node (ref "R48") (pin "2") (pinfunction "2_2") (pintype "passive"))
    )
    (net (code "74") (name "/PIN141") (class "Default")
      (node (ref "R39") (pin "2") (pinfunction "2_2") (pintype "passive"))
    )
    (net (code "75") (name "/PIN142") (class "Default")
      (node (ref "R29") (pin "2") (pinfunction "2_2") (pintype "passive"))
    )
    (net (code "76") (name "/PIN143") (class "Default")
      (node (ref "R30") (pin "2") (pinfunction "2_2") (pintype "passive"))
    )
    (net (code "77") (name "Net-(D1-B)") (class "Default")
      (node (ref "D1") (pin "3") (pinfunction "B_3") (pintype "passive"))
      (node (ref "R19") (pin "1") (pinfunction "1_1") (pintype "passive"))
    )
    (net (code "78") (name "Net-(D1-G)") (class "Default")
      (node (ref "D1") (pin "2") (pinfunction "G_2") (pintype "passive"))
      (node (ref "R10") (pin "1") (pinfunction "1_1") (pintype "passive"))
    )
    (net (code "79") (name "Net-(D1-R)") (class "Default")
      (node (ref "D1") (pin "1") (pinfunction "R_1") (pintype "passive"))
      (node (ref "R1") (pin "1") (pinfunction "1_1") (pintype "passive"))
    )
    (net (code "80") (name "Net-(D2-B)") (class "Default")
      (node (ref "D2") (pin "3") (pinfunction "B_3") (pintype "passive"))
      (node (ref "R20") (pin "1") (pinfunction "1_1") (pintype "passive"))
    )
    (net (code "81") (name "Net-(D2-G)") (class "Default")
      (node (ref "D2") (pin "2") (pinfunction "G_2") (pintype "passive"))
      (node (ref "R11") (pin "1") (pinfunction "1_1") (pintype "passive"))
    )
    (net (code "82") (name "Net-(D2-R)") (class "Default")
      (node (ref "D2") (pin "1") (pinfunction "R_1") (pintype "passive"))
      (node (ref "R2") (pin "1") (pinfunction "1_1") (pintype "passive"))
    )
    (net (code "83") (name "Net-(D3-B)") (class "Default")
      (node (ref "D3") (pin "3") (pinfunction "B_3") (pintype "passive"))
      (node (ref "R21") (pin "1") (pinfunction "1_1") (pintype "passive"))
    )
    (net (code "84") (name "Net-(D3-G)") (class "Default")
      (node (ref "D3") (pin "2") (pinfunction "G_2") (pintype "passive"))
      (node (ref "R12") (pin "1") (pinfunction "1_1") (pintype "passive"))
    )
    (net (code "85") (name "Net-(D3-R)") (class "Default")
      (node (ref "D3") (pin "1") (pinfunction "R_1") (pintype "passive"))
      (node (ref "R3") (pin "1") (pinfunction "1_1") (pintype "passive"))
    )
    (net (code "86") (name "Net-(D4-B)") (class "Default")
      (node (ref "D4") (pin "3") (pinfunction "B_3") (pintype "passive"))
      (node (ref "R22") (pin "1") (pinfunction "1_1") (pintype "passive"))
    )
    (net (code "87") (name "Net-(D4-G)") (class "Default")
      (node (ref "D4") (pin "2") (pinfunction "G_2") (pintype "passive"))
      (node (ref "R13") (pin "1") (pinfunction "1_1") (pintype "passive"))
    )
    (net (code "88") (name "Net-(D4-R)") (class "Default")
      (node (ref "D4") (pin "1") (pinfunction "R_1") (pintype "passive"))
      (node (ref "R4") (pin "1") (pinfunction "1_1") (pintype "passive"))
    )
    (net (code "89") (name "Net-(D5-B)") (class "Default")
      (node (ref "D5") (pin "3") (pinfunction "B_3") (pintype "passive"))
      (node (ref "R23") (pin "1") (pinfunction "1_1") (pintype "passive"))
    )
    (net (code "90") (name "Net-(D5-G)") (class "Default")
      (node (ref "D5") (pin "2") (pinfunction "G_2") (pintype "passive"))
      (node (ref "R14") (pin "1") (pinfunction "1_1") (pintype "passive"))
    )
    (net (code "91") (name "Net-(D5-R)") (class "Default")
      (node (ref "D5") (pin "1") (pinfunction "R_1") (pintype "passive"))
      (node (ref "R5") (pin "1") (pinfunction "1_1") (pintype "passive"))
    )
    (net (code "92") (name "Net-(D6-B)") (class "Default")
      (node (ref "D6") (pin "3") (pinfunction "B_3") (pintype "passive"))
      (node (ref "R24") (pin "1") (pinfunction "1_1") (pintype "passive"))
    )
    (net (code "93") (name "Net-(D6-G)") (class "Default")
      (node (ref "D6") (pin "2") (pinfunction "G_2") (pintype "passive"))
      (node (ref "R15") (pin "1") (pinfunction "1_1") (pintype "passive"))
    )
    (net (code "94") (name "Net-(D6-R)") (class "Default")
      (node (ref "D6") (pin "1") (pinfunction "R_1") (pintype "passive"))
      (node (ref "R6") (pin "1") (pinfunction "1_1") (pintype "passive"))
    )
    (net (code "95") (name "Net-(D7-B)") (class "Default")
      (node (ref "D7") (pin "3") (pinfunction "B_3") (pintype "passive"))
      (node (ref "R25") (pin "1") (pinfunction "1_1") (pintype "passive"))
    )
    (net (code "96") (name "Net-(D7-G)") (class "Default")
      (node (ref "D7") (pin "2") (pinfunction "G_2") (pintype "passive"))
      (node (ref "R16") (pin "1") (pinfunction "1_1") (pintype "passive"))
    )
    (net (code "97") (name "Net-(D7-R)") (class "Default")
      (node (ref "D7") (pin "1") (pinfunction "R_1") (pintype "passive"))
      (node (ref "R7") (pin "1") (pinfunction "1_1") (pintype "passive"))
    )
    (net (code "98") (name "Net-(D8-B)") (class "Default")
      (node (ref "D8") (pin "3") (pinfunction "B_3") (pintype "passive"))
      (node (ref "R26") (pin "1") (pinfunction "1_1") (pintype "passive"))
    )
    (net (code "99") (name "Net-(D8-G)") (class "Default")
      (node (ref "D8") (pin "2") (pinfunction "G_2") (pintype "passive"))
      (node (ref "R17") (pin "1") (pinfunction "1_1") (pintype "passive"))
    )
    (net (code "100") (name "Net-(D8-R)") (class "Default")
      (node (ref "D8") (pin "1") (pinfunction "R_1") (pintype "passive"))
      (node (ref "R8") (pin "1") (pinfunction "1_1") (pintype "passive"))
    )
    (net (code "101") (name "Net-(D9-B)") (class "Default")
      (node (ref "D9") (pin "3") (pinfunction "B_3") (pintype "passive"))
      (node (ref "R27") (pin "1") (pinfunction "1_1") (pintype "passive"))
    )
    (net (code "102") (name "Net-(D9-G)") (class "Default")
      (node (ref "D9") (pin "2") (pinfunction "G_2") (pintype "passive"))
      (node (ref "R18") (pin "1") (pinfunction "1_1") (pintype "passive"))
    )
    (net (code "103") (name "Net-(D9-R)") (class "Default")
      (node (ref "D9") (pin "1") (pinfunction "R_1") (pintype "passive"))
      (node (ref "R9") (pin "1") (pinfunction "1_1") (pintype "passive"))
    )
    (net (code "104") (name "Net-(D10-B)") (class "Default")
      (node (ref "D10") (pin "3") (pinfunction "B_3") (pintype "passive"))
      (node (ref "R46") (pin "1") (pinfunction "1_1") (pintype "passive"))
    )
    (net (code "105") (name "Net-(D10-G)") (class "Default")
      (node (ref "D10") (pin "2") (pinfunction "G_2") (pintype "passive"))
      (node (ref "R37") (pin "1") (pinfunction "1_1") (pintype "passive"))
    )
    (net (code "106") (name "Net-(D10-R)") (class "Default")
      (node (ref "D10") (pin "1") (pinfunction "R_1") (pintype "passive"))
      (node (ref "R28") (pin "1") (pinfunction "1_1") (pintype "passive"))
    )
    (net (code "107") (name "Net-(D11-B)") (class "Default")
      (node (ref "D11") (pin "3") (pinfunction "B_3") (pintype "passive"))
      (node (ref "R47") (pin "1") (pinfunction "1_1") (pintype "passive"))
    )
    (net (code "108") (name "Net-(D11-G)") (class "Default")
      (node (ref "D11") (pin "2") (pinfunction "G_2") (pintype "passive"))
      (node (ref "R38") (pin "1") (pinfunction "1_1") (pintype "passive"))
    )
    (net (code "109") (name "Net-(D11-R)") (class "Default")
      (node (ref "D11") (pin "1") (pinfunction "R_1") (pintype "passive"))
      (node (ref "R29") (pin "1") (pinfunction "1_1") (pintype "passive"))
    )
    (net (code "110") (name "Net-(D12-B)") (class "Default")
      (node (ref "D12") (pin "3") (pinfunction "B_3") (pintype "passive"))
      (node (ref "R48") (pin "1") (pinfunction "1_1") (pintype "passive"))
    )
    (net (code "111") (name "Net-(D12-G)") (class "Default")
      (node (ref "D12") (pin "2") (pinfunction "G_2") (pintype "passive"))
      (node (ref "R39") (pin "1") (pinfunction "1_1") (pintype "passive"))
    )
    (net (code "112") (name "Net-(D12-R)") (class "Default")
      (node (ref "D12") (pin "1") (pinfunction "R_1") (pintype "passive"))
      (node (ref "R30") (pin "1") (pinfunction "1_1") (pintype "passive"))
    )
    (net (code "113") (name "Net-(D13-B)") (class "Default")
      (node (ref "D13") (pin "3") (pinfunction "B_3") (pintype "passive"))
      (node (ref "R49") (pin "1") (pinfunction "1_1") (pintype "passive"))
    )
    (net (code "114") (name "Net-(D13-G)") (class "Default")
      (node (ref "D13") (pin "2") (pinfunction "G_2") (pintype "passive"))
      (node (ref "R40") (pin "1") (pinfunction "1_1") (pintype "passive"))
    )
    (net (code "115") (name "Net-(D13-R)") (class "Default")
      (node (ref "D13") (pin "1") (pinfunction "R_1") (pintype "passive"))
      (node (ref "R31") (pin "1") (pinfunction "1_1") (pintype "passive"))
    )
    (net (code "116") (name "Net-(D14-B)") (class "Default")
      (node (ref "D14") (pin "3") (pinfunction "B_3") (pintype "passive"))
      (node (ref "R50") (pin "1") (pinfunction "1_1") (pintype "passive"))
    )
    (net (code "117") (name "Net-(D14-G)") (class "Default")
      (node (ref "D14") (pin "2") (pinfunction "G_2") (pintype "passive"))
      (node (ref "R41") (pin "1") (pinfunction "1_1") (pintype "passive"))
    )
    (net (code "118") (name "Net-(D14-R)") (class "Default")
      (node (ref "D14") (pin "1") (pinfunction "R_1") (pintype "passive"))
      (node (ref "R32") (pin "1") (pinfunction "1_1") (pintype "passive"))
    )
    (net (code "119") (name "Net-(D15-B)") (class "Default")
      (node (ref "D15") (pin "3") (pinfunction "B_3") (pintype "passive"))
      (node (ref "R51") (pin "1") (pinfunction "1_1") (pintype "passive"))
    )
    (net (code "120") (name "Net-(D15-G)") (class "Default")
      (node (ref "D15") (pin "2") (pinfunction "G_2") (pintype "passive"))
      (node (ref "R42") (pin "1") (pinfunction "1_1") (pintype "passive"))
    )
    (net (code "121") (name "Net-(D15-R)") (class "Default")
      (node (ref "D15") (pin "1") (pinfunction "R_1") (pintype "passive"))
      (node (ref "R33") (pin "1") (pinfunction "1_1") (pintype "passive"))
    )
    (net (code "122") (name "Net-(D16-B)") (class "Default")
      (node (ref "D16") (pin "3") (pinfunction "B_3") (pintype "passive"))
      (node (ref "R52") (pin "1") (pinfunction "1_1") (pintype "passive"))
    )
    (net (code "123") (name "Net-(D16-G)") (class "Default")
      (node (ref "D16") (pin "2") (pinfunction "G_2") (pintype "passive"))
      (node (ref "R43") (pin "1") (pinfunction "1_1") (pintype "passive"))
    )
    (net (code "124") (name "Net-(D16-R)") (class "Default")
      (node (ref "D16") (pin "1") (pinfunction "R_1") (pintype "passive"))
      (node (ref "R34") (pin "1") (pinfunction "1_1") (pintype "passive"))
    )
    (net (code "125") (name "Net-(D17-B)") (class "Default")
      (node (ref "D17") (pin "3") (pinfunction "B_3") (pintype "passive"))
      (node (ref "R53") (pin "1") (pinfunction "1_1") (pintype "passive"))
    )
    (net (code "126") (name "Net-(D17-G)") (class "Default")
      (node (ref "D17") (pin "2") (pinfunction "G_2") (pintype "passive"))
      (node (ref "R44") (pin "1") (pinfunction "1_1") (pintype "passive"))
    )
    (net (code "127") (name "Net-(D17-R)") (class "Default")
      (node (ref "D17") (pin "1") (pinfunction "R_1") (pintype "passive"))
      (node (ref "R35") (pin "1") (pinfunction "1_1") (pintype "passive"))
    )
    (net (code "128") (name "Net-(D18-B)") (class "Default")
      (node (ref "D18") (pin "3") (pinfunction "B_3") (pintype "passive"))
      (node (ref "R54") (pin "1") (pinfunction "1_1") (pintype "passive"))
    )
    (net (code "129") (name "Net-(D18-G)") (class "Default")
      (node (ref "D18") (pin "2") (pinfunction "G_2") (pintype "passive"))
      (node (ref "R45") (pin "1") (pinfunction "1_1") (pintype "passive"))
    )
    (net (code "130") (name "Net-(D18-R)") (class "Default")
      (node (ref "D18") (pin "1") (pinfunction "R_1") (pintype "passive"))
      (node (ref "R36") (pin "1") (pinfunction "1_1") (pintype "passive"))
    )
    (net (code "131") (name "Net-(D19-B)") (class "Default")
      (node (ref "D19") (pin "3") (pinfunction "B_3") (pintype "passive"))
      (node (ref "R69") (pin "1") (pinfunction "1_1") (pintype "passive"))
    )
    (net (code "132") (name "Net-(D19-G)") (class "Default")
      (node (ref "D19") (pin "2") (pinfunction "G_2") (pintype "passive"))
      (node (ref "R62") (pin "1") (pinfunction "1_1") (pintype "passive"))
    )
    (net (code "133") (name "Net-(D19-R)") (class "Default")
      (node (ref "D19") (pin "1") (pinfunction "R_1") (pintype "passive"))
      (node (ref "R55") (pin "1") (pinfunction "1_1") (pintype "passive"))
    )
    (net (code "134") (name "Net-(D20-B)") (class "Default")
      (node (ref "D20") (pin "3") (pinfunction "B_3") (pintype "passive"))
      (node (ref "R70") (pin "1") (pinfunction "1_1") (pintype "passive"))
    )
    (net (code "135") (name "Net-(D20-G)") (class "Default")
      (node (ref "D20") (pin "2") (pinfunction "G_2") (pintype "passive"))
      (node (ref "R63") (pin "1") (pinfunction "1_1") (pintype "passive"))
    )
    (net (code "136") (name "Net-(D20-R)") (class "Default")
      (node (ref "D20") (pin "1") (pinfunction "R_1") (pintype "passive"))
      (node (ref "R56") (pin "1") (pinfunction "1_1") (pintype "passive"))
    )
    (net (code "137") (name "Net-(D21-B)") (class "Default")
      (node (ref "D21") (pin "3") (pinfunction "B_3") (pintype "passive"))
      (node (ref "R71") (pin "1") (pinfunction "1_1") (pintype "passive"))
    )
    (net (code "138") (name "Net-(D21-G)") (class "Default")
      (node (ref "D21") (pin "2") (pinfunction "G_2") (pintype "passive"))
      (node (ref "R64") (pin "1") (pinfunction "1_1") (pintype "passive"))
    )
    (net (code "139") (name "Net-(D21-R)") (class "Default")
      (node (ref "D21") (pin "1") (pinfunction "R_1") (pintype "passive"))
      (node (ref "R57") (pin "1") (pinfunction "1_1") (pintype "passive"))
    )
    (net (code "140") (name "Net-(D22-B)") (class "Default")
      (node (ref "D22") (pin "3") (pinfunction "B_3") (pintype "passive"))
      (node (ref "R72") (pin "1") (pinfunction "1_1") (pintype "passive"))
    )
    (net (code "141") (name "Net-(D22-G)") (class "Default")
      (node (ref "D22") (pin "2") (pinfunction "G_2") (pintype "passive"))
      (node (ref "R65") (pin "1") (pinfunction "1_1") (pintype "passive"))
    )
    (net (code "142") (name "Net-(D22-R)") (class "Default")
      (node (ref "D22") (pin "1") (pinfunction "R_1") (pintype "passive"))
      (node (ref "R58") (pin "1") (pinfunction "1_1") (pintype "passive"))
    )
    (net (code "143") (name "Net-(D23-B)") (class "Default")
      (node (ref "D23") (pin "3") (pinfunction "B_3") (pintype "passive"))
      (node (ref "R73") (pin "1") (pinfunction "1_1") (pintype "passive"))
    )
    (net (code "144") (name "Net-(D23-G)") (class "Default")
      (node (ref "D23") (pin "2") (pinfunction "G_2") (pintype "passive"))
      (node (ref "R66") (pin "1") (pinfunction "1_1") (pintype "passive"))
    )
    (net (code "145") (name "Net-(D23-R)") (class "Default")
      (node (ref "D23") (pin "1") (pinfunction "R_1") (pintype "passive"))
      (node (ref "R59") (pin "1") (pinfunction "1_1") (pintype "passive"))
    )
    (net (code "146") (name "Net-(D24-B)") (class "Default")
      (node (ref "D24") (pin "3") (pinfunction "B_3") (pintype "passive"))
      (node (ref "R74") (pin "1") (pinfunction "1_1") (pintype "passive"))
    )
    (net (code "147") (name "Net-(D24-G)") (class "Default")
      (node (ref "D24") (pin "2") (pinfunction "G_2") (pintype "passive"))
      (node (ref "R67") (pin "1") (pinfunction "1_1") (pintype "passive"))
    )
    (net (code "148") (name "Net-(D24-R)") (class "Default")
      (node (ref "D24") (pin "1") (pinfunction "R_1") (pintype "passive"))
      (node (ref "R60") (pin "1") (pinfunction "1_1") (pintype "passive"))
    )
    (net (code "149") (name "Net-(D25-B)") (class "Default")
      (node (ref "D25") (pin "3") (pinfunction "B_3") (pintype "passive"))
      (node (ref "R75") (pin "1") (pinfunction "1_1") (pintype "passive"))
    )
    (net (code "150") (name "Net-(D25-G)") (class "Default")
      (node (ref "D25") (pin "2") (pinfunction "G_2") (pintype "passive"))
      (node (ref "R68") (pin "1") (pinfunction "1_1") (pintype "passive"))
    )
    (net (code "151") (name "Net-(D25-R)") (class "Default")
      (node (ref "D25") (pin "1") (pinfunction "R_1") (pintype "passive"))
      (node (ref "R61") (pin "1") (pinfunction "1_1") (pintype "passive"))
    )
  )
)
